# RoverWing-cover-V2_0.net
KiCad netlist of a schematic drawn in EAGLE
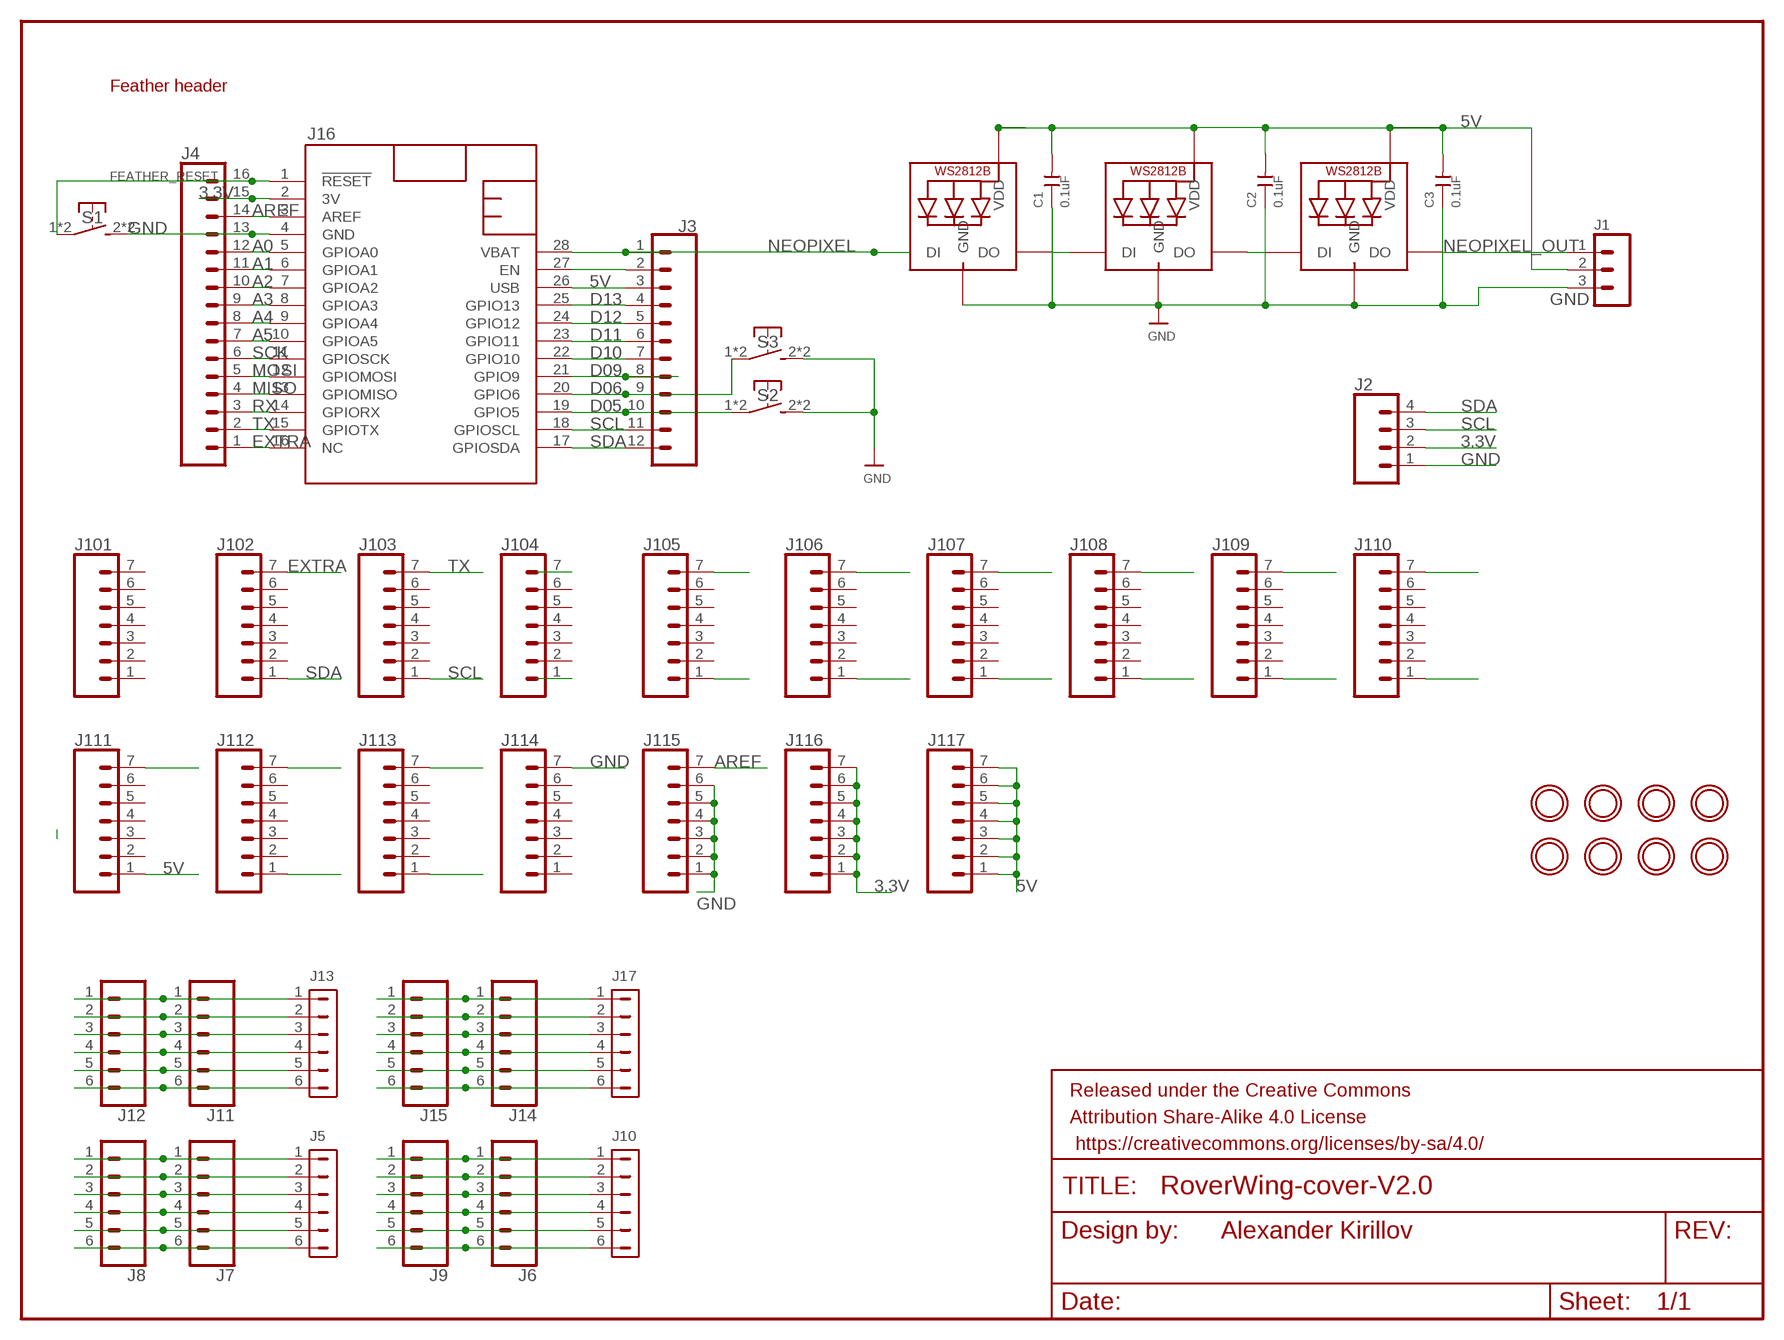
[diagram p0: schematic, sheet 1]

(export (version "E")
  (design (tool "Eeschema 10.0.6"))
  (components
    (comp (ref "C1")
      (value "0.1uF")
      (footprint "eagle-import:C0805")
      (fields (field (name "MF") "AVX") (field (name "MPN") "04025C104KAT2A"))
      (libsource (lib "eagle-import") (part "CAP-CERAMIC-SMD-0805"))
    )
    (comp (ref "C2")
      (value "0.1uF")
      (footprint "eagle-import:C0805")
      (fields (field (name "MF") "AVX") (field (name "MPN") "04025C104KAT2A"))
      (libsource (lib "eagle-import") (part "CAP-CERAMIC-SMD-0805"))
    )
    (comp (ref "C3")
      (value "0.1uF")
      (footprint "eagle-import:C0805")
      (fields (field (name "MF") "AVX") (field (name "MPN") "04025C104KAT2A"))
      (libsource (lib "eagle-import") (part "CAP-CERAMIC-SMD-0805"))
    )
    (comp (ref "FRAME2")
      (value "FRAME-LETTERNO_PACKAGE")
      (footprint "eagle-import:DUMMY")
      (fields (field (name "OC_NEWARK") "unknown") (field (name "DESIGNER") "Nobody"))
      (libsource (lib "eagle-import") (part "FRAME-LETTERNO_PACKAGE"))
    )
    (comp (ref "J1")
      (value "HEADER-PH-3PSIDEENTRY")
      (footprint "eagle-import:S3B-PH-K")
      (fields
        (field (name "PARTNO") "S3B-PH-K-S(LF)(SN)")
        (field (name "MF") "JST (JAPAN SOLDERLESS TERMINALS)")
        (field (name "MPN") "S3B-PH-K-S (LF)(SN)")
      )
      (libsource (lib "eagle-import") (part "HEADER-PH-3PSIDEENTRY"))
    )
    (comp (ref "J2")
      (value "CONN_04")
      (footprint "eagle-import:1X04")
      (libsource (lib "eagle-import") (part "CONN_04"))
    )
    (comp (ref "J3")
      (value "CONN_12NO_SILK")
      (footprint "eagle-import:1X12_NO_SILK")
      (libsource (lib "eagle-import") (part "CONN_12NO_SILK"))
    )
    (comp (ref "J4")
      (value "CONN_161X16_NO_SILK")
      (footprint "eagle-import:1X16_NO_SILK")
      (libsource (lib "eagle-import") (part "CONN_161X16_NO_SILK"))
    )
    (comp (ref "J5")
      (value "HEADER-PH-6PSIDEENTRY")
      (footprint "eagle-import:S6B-PH-K")
      (libsource (lib "eagle-import") (part "HEADER-PH-6PSIDEENTRY"))
    )
    (comp (ref "J6")
      (value "CONN_06NO_SILK_NO_POP")
      (footprint "eagle-import:1X06_NO_SILK")
      (libsource (lib "eagle-import") (part "CONN_06NO_SILK_NO_POP"))
    )
    (comp (ref "J7")
      (value "CONN_06NO_SILK_NO_POP")
      (footprint "eagle-import:1X06_NO_SILK")
      (libsource (lib "eagle-import") (part "CONN_06NO_SILK_NO_POP"))
    )
    (comp (ref "J8")
      (value "CONN_06NO_SILK_NO_POP")
      (footprint "eagle-import:1X06_NO_SILK")
      (libsource (lib "eagle-import") (part "CONN_06NO_SILK_NO_POP"))
    )
    (comp (ref "J9")
      (value "CONN_06NO_SILK_NO_POP")
      (footprint "eagle-import:1X06_NO_SILK")
      (libsource (lib "eagle-import") (part "CONN_06NO_SILK_NO_POP"))
    )
    (comp (ref "J10")
      (value "HEADER-PH-6PSIDEENTRY")
      (footprint "eagle-import:S6B-PH-K")
      (libsource (lib "eagle-import") (part "HEADER-PH-6PSIDEENTRY"))
    )
    (comp (ref "J11")
      (value "CONN_06NO_SILK_NO_POP")
      (footprint "eagle-import:1X06_NO_SILK")
      (libsource (lib "eagle-import") (part "CONN_06NO_SILK_NO_POP"))
    )
    (comp (ref "J12")
      (value "CONN_06NO_SILK_NO_POP")
      (footprint "eagle-import:1X06_NO_SILK")
      (libsource (lib "eagle-import") (part "CONN_06NO_SILK_NO_POP"))
    )
    (comp (ref "J13")
      (value "HEADER-PH-6PSIDEENTRY")
      (footprint "eagle-import:S6B-PH-K")
      (libsource (lib "eagle-import") (part "HEADER-PH-6PSIDEENTRY"))
    )
    (comp (ref "J14")
      (value "CONN_06NO_SILK_NO_POP")
      (footprint "eagle-import:1X06_NO_SILK")
      (libsource (lib "eagle-import") (part "CONN_06NO_SILK_NO_POP"))
    )
    (comp (ref "J15")
      (value "CONN_06NO_SILK_NO_POP")
      (footprint "eagle-import:1X06_NO_SILK")
      (libsource (lib "eagle-import") (part "CONN_06NO_SILK_NO_POP"))
    )
    (comp (ref "J16")
      (value "FEATHERWING_NODIM")
      (footprint "eagle-import:FEATHERWING_DIM")
      (libsource (lib "eagle-import") (part "FEATHERWING_NODIM"))
    )
    (comp (ref "J17")
      (value "HEADER-PH-6PSIDEENTRY")
      (footprint "eagle-import:S6B-PH-K")
      (libsource (lib "eagle-import") (part "HEADER-PH-6PSIDEENTRY"))
    )
    (comp (ref "J101")
      (value "CONN_07NO_SILK")
      (footprint "eagle-import:1X07_NO_SILK")
      (libsource (lib "eagle-import") (part "CONN_07NO_SILK"))
    )
    (comp (ref "J102")
      (value "CONN_07NO_SILK")
      (footprint "eagle-import:1X07_NO_SILK")
      (libsource (lib "eagle-import") (part "CONN_07NO_SILK"))
    )
    (comp (ref "J103")
      (value "CONN_07NO_SILK")
      (footprint "eagle-import:1X07_NO_SILK")
      (libsource (lib "eagle-import") (part "CONN_07NO_SILK"))
    )
    (comp (ref "J104")
      (value "CONN_07NO_SILK")
      (footprint "eagle-import:1X07_NO_SILK")
      (libsource (lib "eagle-import") (part "CONN_07NO_SILK"))
    )
    (comp (ref "J105")
      (value "CONN_07NO_SILK")
      (footprint "eagle-import:1X07_NO_SILK")
      (libsource (lib "eagle-import") (part "CONN_07NO_SILK"))
    )
    (comp (ref "J106")
      (value "CONN_07NO_SILK")
      (footprint "eagle-import:1X07_NO_SILK")
      (libsource (lib "eagle-import") (part "CONN_07NO_SILK"))
    )
    (comp (ref "J107")
      (value "CONN_07NO_SILK")
      (footprint "eagle-import:1X07_NO_SILK")
      (libsource (lib "eagle-import") (part "CONN_07NO_SILK"))
    )
    (comp (ref "J108")
      (value "CONN_07NO_SILK")
      (footprint "eagle-import:1X07_NO_SILK")
      (libsource (lib "eagle-import") (part "CONN_07NO_SILK"))
    )
    (comp (ref "J109")
      (value "CONN_07NO_SILK")
      (footprint "eagle-import:1X07_NO_SILK")
      (libsource (lib "eagle-import") (part "CONN_07NO_SILK"))
    )
    (comp (ref "J110")
      (value "CONN_07NO_SILK")
      (footprint "eagle-import:1X07_NO_SILK")
      (libsource (lib "eagle-import") (part "CONN_07NO_SILK"))
    )
    (comp (ref "J111")
      (value "CONN_07NO_SILK")
      (footprint "eagle-import:1X07_NO_SILK")
      (libsource (lib "eagle-import") (part "CONN_07NO_SILK"))
    )
    (comp (ref "J112")
      (value "CONN_07NO_SILK")
      (footprint "eagle-import:1X07_NO_SILK")
      (libsource (lib "eagle-import") (part "CONN_07NO_SILK"))
    )
    (comp (ref "J113")
      (value "CONN_07NO_SILK")
      (footprint "eagle-import:1X07_NO_SILK")
      (libsource (lib "eagle-import") (part "CONN_07NO_SILK"))
    )
    (comp (ref "J114")
      (value "CONN_07NO_SILK")
      (footprint "eagle-import:1X07_NO_SILK")
      (libsource (lib "eagle-import") (part "CONN_07NO_SILK"))
    )
    (comp (ref "J115")
      (value "CONN_07NO_SILK")
      (footprint "eagle-import:1X07_NO_SILK")
      (libsource (lib "eagle-import") (part "CONN_07NO_SILK"))
    )
    (comp (ref "J116")
      (value "CONN_07NO_SILK")
      (footprint "eagle-import:1X07_NO_SILK")
      (libsource (lib "eagle-import") (part "CONN_07NO_SILK"))
    )
    (comp (ref "J117")
      (value "CONN_07NO_SILK")
      (footprint "eagle-import:1X07_NO_SILK")
      (libsource (lib "eagle-import") (part "CONN_07NO_SILK"))
    )
    (comp (ref "LED1")
      (value "WS2812B3535")
      (footprint "eagle-import:LED3535")
      (fields
        (field (name "MANUFACTURER") "Worldsemi")
        (field (name "PARTNO") "WS2812B-3535 ")
        (field (name "MF") "ADAFRUIT")
      )
      (libsource (lib "eagle-import") (part "WS2812B3535"))
    )
    (comp (ref "LED2")
      (value "WS2812B3535")
      (footprint "eagle-import:LED3535")
      (fields
        (field (name "MANUFACTURER") "Worldsemi")
        (field (name "PARTNO") "WS2812B-3535 ")
        (field (name "MF") "ADAFRUIT")
      )
      (libsource (lib "eagle-import") (part "WS2812B3535"))
    )
    (comp (ref "LED3")
      (value "WS2812B3535")
      (footprint "eagle-import:LED3535")
      (fields
        (field (name "MANUFACTURER") "Worldsemi")
        (field (name "PARTNO") "WS2812B-3535 ")
        (field (name "MF") "ADAFRUIT")
      )
      (libsource (lib "eagle-import") (part "WS2812B3535"))
    )
    (comp (ref "S1")
      (value "SW-TACTILE-4.5X4.5_SMD")
      (footprint "eagle-import:TL3305")
      (fields (field (name "MF") "E-SWITCH") (field (name "MPN") "TL3305AF160QG"))
      (libsource (lib "eagle-import") (part "SW-TACTILE-4.5X4.5_SMD"))
    )
    (comp (ref "S2")
      (value "SW-TACTILE-4.5X4.5_SMD")
      (footprint "eagle-import:TL3305")
      (fields (field (name "MF") "E-SWITCH") (field (name "MPN") "TL3305AF160QG"))
      (libsource (lib "eagle-import") (part "SW-TACTILE-4.5X4.5_SMD"))
    )
    (comp (ref "S3")
      (value "SW-TACTILE-4.5X4.5_SMD")
      (footprint "eagle-import:TL3305")
      (fields (field (name "MF") "E-SWITCH") (field (name "MPN") "TL3305AF160QG"))
      (libsource (lib "eagle-import") (part "SW-TACTILE-4.5X4.5_SMD"))
    )
    (comp (ref "U$3")
      (value "MOUNTINGHOLE3.0_NPH")
      (footprint "eagle-import:MOUNTINGHOLE_3.0_NPH")
      (libsource (lib "eagle-import") (part "MOUNTINGHOLE3.0_NPH"))
    )
    (comp (ref "U$4")
      (value "MOUNTINGHOLE3.0_NPH")
      (footprint "eagle-import:MOUNTINGHOLE_3.0_NPH")
      (libsource (lib "eagle-import") (part "MOUNTINGHOLE3.0_NPH"))
    )
    (comp (ref "U$14")
      (value "MOUNTINGHOLE3.0_NPH")
      (footprint "eagle-import:MOUNTINGHOLE_3.0_NPH")
      (libsource (lib "eagle-import") (part "MOUNTINGHOLE3.0_NPH"))
    )
    (comp (ref "U$15")
      (value "MOUNTINGHOLE3.0_NPH")
      (footprint "eagle-import:MOUNTINGHOLE_3.0_NPH")
      (libsource (lib "eagle-import") (part "MOUNTINGHOLE3.0_NPH"))
    )
    (comp (ref "U$24")
      (value "MOUNTINGHOLE3.0_NPH")
      (footprint "eagle-import:MOUNTINGHOLE_3.0_NPH")
      (libsource (lib "eagle-import") (part "MOUNTINGHOLE3.0_NPH"))
    )
    (comp (ref "U$25")
      (value "MOUNTINGHOLE3.0_NPH")
      (footprint "eagle-import:MOUNTINGHOLE_3.0_NPH")
      (libsource (lib "eagle-import") (part "MOUNTINGHOLE3.0_NPH"))
    )
    (comp (ref "U$26")
      (value "MOUNTINGHOLE3.0_NPH")
      (footprint "eagle-import:MOUNTINGHOLE_3.0_NPH")
      (libsource (lib "eagle-import") (part "MOUNTINGHOLE3.0_NPH"))
    )
    (comp (ref "U$27")
      (value "MOUNTINGHOLE3.0_NPH")
      (footprint "eagle-import:MOUNTINGHOLE_3.0_NPH")
      (libsource (lib "eagle-import") (part "MOUNTINGHOLE3.0_NPH"))
    )
  )
  (nets
    (net (code "1") (name "/3.3V") (class "Default")
      (node (ref "J116") (pin "1") (pinfunction "1_1") (pintype "passive"))
      (node (ref "J116") (pin "2") (pinfunction "2_2") (pintype "passive"))
      (node (ref "J116") (pin "3") (pinfunction "3_3") (pintype "passive"))
      (node (ref "J116") (pin "4") (pinfunction "4_4") (pintype "passive"))
      (node (ref "J116") (pin "5") (pinfunction "5_5") (pintype "passive"))
      (node (ref "J116") (pin "6") (pinfunction "6_6") (pintype "passive"))
      (node (ref "J116") (pin "7") (pinfunction "7_7") (pintype "passive"))
      (node (ref "J16") (pin "2") (pinfunction "3V_2") (pintype "power_in"))
      (node (ref "J2") (pin "2") (pinfunction "2_2") (pintype "passive"))
      (node (ref "J4") (pin "15") (pinfunction "15_15") (pintype "passive"))
    )
    (net (code "2") (name "/5V") (class "Default")
      (node (ref "C1") (pin "2") (pinfunction "2_2") (pintype "passive"))
      (node (ref "C2") (pin "2") (pinfunction "2_2") (pintype "passive"))
      (node (ref "C3") (pin "2") (pinfunction "2_2") (pintype "passive"))
      (node (ref "J1") (pin "2") (pinfunction "2_2") (pintype "passive"))
      (node (ref "J111") (pin "1") (pinfunction "1_1") (pintype "passive"))
      (node (ref "J117") (pin "1") (pinfunction "1_1") (pintype "passive"))
      (node (ref "J117") (pin "2") (pinfunction "2_2") (pintype "passive"))
      (node (ref "J117") (pin "3") (pinfunction "3_3") (pintype "passive"))
      (node (ref "J117") (pin "4") (pinfunction "4_4") (pintype "passive"))
      (node (ref "J117") (pin "5") (pinfunction "5_5") (pintype "passive"))
      (node (ref "J117") (pin "6") (pinfunction "6_6") (pintype "passive"))
      (node (ref "J117") (pin "7") (pinfunction "7_7") (pintype "passive"))
      (node (ref "J16") (pin "26") (pinfunction "USB_26") (pintype "power_in"))
      (node (ref "J3") (pin "3") (pinfunction "3_3") (pintype "passive"))
      (node (ref "LED1") (pin "3") (pinfunction "VDD_3") (pintype "power_in"))
      (node (ref "LED2") (pin "3") (pinfunction "VDD_3") (pintype "power_in"))
      (node (ref "LED3") (pin "3") (pinfunction "VDD_3") (pintype "power_in"))
    )
    (net (code "3") (name "/A0") (class "Default")
      (node (ref "J113") (pin "7") (pinfunction "7_7") (pintype "passive"))
      (node (ref "J16") (pin "5") (pinfunction "GPIOA0_5") (pintype "bidirectional"))
      (node (ref "J4") (pin "12") (pinfunction "12_12") (pintype "passive"))
    )
    (net (code "4") (name "/A1") (class "Default")
      (node (ref "J112") (pin "7") (pinfunction "7_7") (pintype "passive"))
      (node (ref "J16") (pin "6") (pinfunction "GPIOA1_6") (pintype "bidirectional"))
      (node (ref "J4") (pin "11") (pinfunction "11_11") (pintype "passive"))
    )
    (net (code "5") (name "/A2") (class "Default")
      (node (ref "J111") (pin "7") (pinfunction "7_7") (pintype "passive"))
      (node (ref "J16") (pin "7") (pinfunction "GPIOA2_7") (pintype "bidirectional"))
      (node (ref "J4") (pin "10") (pinfunction "10_10") (pintype "passive"))
    )
    (net (code "6") (name "/A3") (class "Default")
      (node (ref "J110") (pin "7") (pinfunction "7_7") (pintype "passive"))
      (node (ref "J16") (pin "8") (pinfunction "GPIOA3_8") (pintype "bidirectional"))
      (node (ref "J4") (pin "9") (pinfunction "9_9") (pintype "passive"))
    )
    (net (code "7") (name "/A4") (class "Default")
      (node (ref "J109") (pin "7") (pinfunction "7_7") (pintype "passive"))
      (node (ref "J16") (pin "9") (pinfunction "GPIOA4_9") (pintype "bidirectional"))
      (node (ref "J4") (pin "8") (pinfunction "8_8") (pintype "passive"))
    )
    (net (code "8") (name "/A5") (class "Default")
      (node (ref "J108") (pin "7") (pinfunction "7_7") (pintype "passive"))
      (node (ref "J16") (pin "10") (pinfunction "GPIOA5_10") (pintype "bidirectional"))
      (node (ref "J4") (pin "7") (pinfunction "7_7") (pintype "passive"))
    )
    (net (code "9") (name "/AREF") (class "Default")
      (node (ref "J115") (pin "7") (pinfunction "7_7") (pintype "passive"))
      (node (ref "J16") (pin "3") (pinfunction "AREF_3") (pintype "passive"))
      (node (ref "J4") (pin "14") (pinfunction "14_14") (pintype "passive"))
    )
    (net (code "10") (name "/D05") (class "Default")
      (node (ref "J104") (pin "1") (pinfunction "1_1") (pintype "passive"))
      (node (ref "J16") (pin "19") (pinfunction "GPIO5_19") (pintype "bidirectional"))
      (node (ref "J3") (pin "10") (pinfunction "10_10") (pintype "passive"))
      (node (ref "S2") (pin "1") (pinfunction "P1_1") (pintype "passive"))
      (node (ref "S2") (pin "4") (pinfunction "P1_4") (pintype "passive"))
    )
    (net (code "11") (name "/D06") (class "Default")
      (node (ref "J105") (pin "1") (pinfunction "1_1") (pintype "passive"))
      (node (ref "J16") (pin "20") (pinfunction "GPIO6_20") (pintype "bidirectional"))
      (node (ref "J3") (pin "9") (pinfunction "9_9") (pintype "passive"))
      (node (ref "S3") (pin "1") (pinfunction "P1_1") (pintype "passive"))
      (node (ref "S3") (pin "4") (pinfunction "P1_4") (pintype "passive"))
    )
    (net (code "12") (name "/D09") (class "Default")
      (node (ref "J106") (pin "1") (pinfunction "1_1") (pintype "passive"))
      (node (ref "J16") (pin "21") (pinfunction "GPIO9_21") (pintype "bidirectional"))
      (node (ref "J3") (pin "8") (pinfunction "8_8") (pintype "passive"))
    )
    (net (code "13") (name "/D10") (class "Default")
      (node (ref "J107") (pin "1") (pinfunction "1_1") (pintype "passive"))
      (node (ref "J16") (pin "22") (pinfunction "GPIO10_22") (pintype "bidirectional"))
      (node (ref "J3") (pin "7") (pinfunction "7_7") (pintype "passive"))
    )
    (net (code "14") (name "/D11") (class "Default")
      (node (ref "J108") (pin "1") (pinfunction "1_1") (pintype "passive"))
      (node (ref "J16") (pin "23") (pinfunction "GPIO11_23") (pintype "bidirectional"))
      (node (ref "J3") (pin "6") (pinfunction "6_6") (pintype "passive"))
    )
    (net (code "15") (name "/D12") (class "Default")
      (node (ref "J109") (pin "1") (pinfunction "1_1") (pintype "passive"))
      (node (ref "J16") (pin "24") (pinfunction "GPIO12_24") (pintype "bidirectional"))
      (node (ref "J3") (pin "5") (pinfunction "5_5") (pintype "passive"))
    )
    (net (code "16") (name "/D13") (class "Default")
      (node (ref "J110") (pin "1") (pinfunction "1_1") (pintype "passive"))
      (node (ref "J16") (pin "25") (pinfunction "GPIO13_25") (pintype "bidirectional"))
      (node (ref "J3") (pin "4") (pinfunction "4_4") (pintype "passive"))
    )
    (net (code "17") (name "/EXTRA") (class "Default")
      (node (ref "J102") (pin "7") (pinfunction "7_7") (pintype "passive"))
      (node (ref "J16") (pin "16") (pinfunction "NC_16") (pintype "passive"))
      (node (ref "J4") (pin "1") (pinfunction "1_1") (pintype "passive"))
    )
    (net (code "18") (name "/FEATHER_RESET") (class "Default")
      (node (ref "J16") (pin "1") (pinfunction "~{RESET}_1") (pintype "input"))
      (node (ref "J4") (pin "16") (pinfunction "16_16") (pintype "passive"))
      (node (ref "S1") (pin "1") (pinfunction "P1_1") (pintype "passive"))
      (node (ref "S1") (pin "4") (pinfunction "P1_4") (pintype "passive"))
    )
    (net (code "19") (name "/MISO") (class "Default")
      (node (ref "J105") (pin "7") (pinfunction "7_7") (pintype "passive"))
      (node (ref "J16") (pin "13") (pinfunction "GPIOMISO_13") (pintype "bidirectional"))
      (node (ref "J4") (pin "4") (pinfunction "4_4") (pintype "passive"))
    )
    (net (code "20") (name "/MOSI") (class "Default")
      (node (ref "J106") (pin "7") (pinfunction "7_7") (pintype "passive"))
      (node (ref "J16") (pin "12") (pinfunction "GPIOMOSI_12") (pintype "bidirectional"))
      (node (ref "J4") (pin "5") (pinfunction "5_5") (pintype "passive"))
    )
    (net (code "21") (name "/N$37") (class "Default")
      (node (ref "J112") (pin "1") (pinfunction "1_1") (pintype "passive"))
      (node (ref "J16") (pin "27") (pinfunction "EN_27") (pintype "passive"))
      (node (ref "J3") (pin "2") (pinfunction "2_2") (pintype "passive"))
    )
    (net (code "22") (name "/NEOPIXEL") (class "Default")
      (node (ref "J16") (pin "28") (pinfunction "VBAT_28") (pintype "power_in"))
      (node (ref "J3") (pin "1") (pinfunction "1_1") (pintype "passive"))
      (node (ref "LED1") (pin "2") (pinfunction "DI_2") (pintype "input"))
    )
    (net (code "23") (name "/NEOPIXEL_OUT") (class "Default")
      (node (ref "J1") (pin "1") (pinfunction "1_1") (pintype "passive"))
      (node (ref "LED3") (pin "4") (pinfunction "DO_4") (pintype "output"))
    )
    (net (code "24") (name "/RX") (class "Default")
      (node (ref "J104") (pin "7") (pinfunction "7_7") (pintype "passive"))
      (node (ref "J16") (pin "14") (pinfunction "GPIORX_14") (pintype "bidirectional"))
      (node (ref "J4") (pin "3") (pinfunction "3_3") (pintype "passive"))
    )
    (net (code "25") (name "/SCK") (class "Default")
      (node (ref "J107") (pin "7") (pinfunction "7_7") (pintype "passive"))
      (node (ref "J16") (pin "11") (pinfunction "GPIOSCK_11") (pintype "bidirectional"))
      (node (ref "J4") (pin "6") (pinfunction "6_6") (pintype "passive"))
    )
    (net (code "26") (name "/SCL") (class "Default")
      (node (ref "J103") (pin "1") (pinfunction "1_1") (pintype "passive"))
      (node (ref "J16") (pin "18") (pinfunction "GPIOSCL_18") (pintype "bidirectional"))
      (node (ref "J2") (pin "3") (pinfunction "3_3") (pintype "passive"))
      (node (ref "J3") (pin "11") (pinfunction "11_11") (pintype "passive"))
    )
    (net (code "27") (name "/SDA") (class "Default")
      (node (ref "J102") (pin "1") (pinfunction "1_1") (pintype "passive"))
      (node (ref "J16") (pin "17") (pinfunction "GPIOSDA_17") (pintype "bidirectional"))
      (node (ref "J2") (pin "4") (pinfunction "4_4") (pintype "passive"))
      (node (ref "J3") (pin "12") (pinfunction "12_12") (pintype "passive"))
    )
    (net (code "28") (name "/TX") (class "Default")
      (node (ref "J103") (pin "7") (pinfunction "7_7") (pintype "passive"))
      (node (ref "J16") (pin "15") (pinfunction "GPIOTX_15") (pintype "bidirectional"))
      (node (ref "J4") (pin "2") (pinfunction "2_2") (pintype "passive"))
    )
    (net (code "29") (name "GND") (class "Default")
      (node (ref "C1") (pin "1") (pinfunction "1_1") (pintype "passive"))
      (node (ref "C2") (pin "1") (pinfunction "1_1") (pintype "passive"))
      (node (ref "C3") (pin "1") (pinfunction "1_1") (pintype "passive"))
      (node (ref "J1") (pin "3") (pinfunction "3_3") (pintype "passive"))
      (node (ref "J114") (pin "7") (pinfunction "7_7") (pintype "passive"))
      (node (ref "J115") (pin "1") (pinfunction "1_1") (pintype "passive"))
      (node (ref "J115") (pin "2") (pinfunction "2_2") (pintype "passive"))
      (node (ref "J115") (pin "3") (pinfunction "3_3") (pintype "passive"))
      (node (ref "J115") (pin "4") (pinfunction "4_4") (pintype "passive"))
      (node (ref "J115") (pin "5") (pinfunction "5_5") (pintype "passive"))
      (node (ref "J115") (pin "6") (pinfunction "6_6") (pintype "passive"))
      (node (ref "J16") (pin "4") (pinfunction "GND_4") (pintype "power_in"))
      (node (ref "J2") (pin "1") (pinfunction "1_1") (pintype "passive"))
      (node (ref "J4") (pin "13") (pinfunction "13_13") (pintype "passive"))
      (node (ref "LED1") (pin "1") (pinfunction "GND_1") (pintype "power_in"))
      (node (ref "LED2") (pin "1") (pinfunction "GND_1") (pintype "power_in"))
      (node (ref "LED3") (pin "1") (pinfunction "GND_1") (pintype "power_in"))
      (node (ref "S1") (pin "2") (pinfunction "S1_2") (pintype "passive"))
      (node (ref "S1") (pin "3") (pinfunction "S1_3") (pintype "passive"))
      (node (ref "S2") (pin "2") (pinfunction "S1_2") (pintype "passive"))
      (node (ref "S2") (pin "3") (pinfunction "S1_3") (pintype "passive"))
      (node (ref "S3") (pin "2") (pinfunction "S1_2") (pintype "passive"))
      (node (ref "S3") (pin "3") (pinfunction "S1_3") (pintype "passive"))
    )
    (net (code "30") (name "Net-(J5-Pad1)") (class "Default")
      (node (ref "J5") (pin "1") (pinfunction "1_1") (pintype "passive"))
      (node (ref "J7") (pin "1") (pinfunction "1_1") (pintype "passive"))
      (node (ref "J8") (pin "1") (pinfunction "1_1") (pintype "passive"))
    )
    (net (code "31") (name "Net-(J5-Pad2)") (class "Default")
      (node (ref "J5") (pin "2") (pinfunction "2_2") (pintype "passive"))
      (node (ref "J7") (pin "2") (pinfunction "2_2") (pintype "passive"))
      (node (ref "J8") (pin "2") (pinfunction "2_2") (pintype "passive"))
    )
    (net (code "32") (name "Net-(J5-Pad3)") (class "Default")
      (node (ref "J5") (pin "3") (pinfunction "3_3") (pintype "passive"))
      (node (ref "J7") (pin "3") (pinfunction "3_3") (pintype "passive"))
      (node (ref "J8") (pin "3") (pinfunction "3_3") (pintype "passive"))
    )
    (net (code "33") (name "Net-(J5-Pad4)") (class "Default")
      (node (ref "J5") (pin "4") (pinfunction "4_4") (pintype "passive"))
      (node (ref "J7") (pin "4") (pinfunction "4_4") (pintype "passive"))
      (node (ref "J8") (pin "4") (pinfunction "4_4") (pintype "passive"))
    )
    (net (code "34") (name "Net-(J5-Pad5)") (class "Default")
      (node (ref "J5") (pin "5") (pinfunction "5_5") (pintype "passive"))
      (node (ref "J7") (pin "5") (pinfunction "5_5") (pintype "passive"))
      (node (ref "J8") (pin "5") (pinfunction "5_5") (pintype "passive"))
    )
    (net (code "35") (name "Net-(J5-Pad6)") (class "Default")
      (node (ref "J5") (pin "6") (pinfunction "6_6") (pintype "passive"))
      (node (ref "J7") (pin "6") (pinfunction "6_6") (pintype "passive"))
      (node (ref "J8") (pin "6") (pinfunction "6_6") (pintype "passive"))
    )
    (net (code "36") (name "Net-(J10-Pad1)") (class "Default")
      (node (ref "J10") (pin "1") (pinfunction "1_1") (pintype "passive"))
      (node (ref "J6") (pin "1") (pinfunction "1_1") (pintype "passive"))
      (node (ref "J9") (pin "1") (pinfunction "1_1") (pintype "passive"))
    )
    (net (code "37") (name "Net-(J10-Pad2)") (class "Default")
      (node (ref "J10") (pin "2") (pinfunction "2_2") (pintype "passive"))
      (node (ref "J6") (pin "2") (pinfunction "2_2") (pintype "passive"))
      (node (ref "J9") (pin "2") (pinfunction "2_2") (pintype "passive"))
    )
    (net (code "38") (name "Net-(J10-Pad3)") (class "Default")
      (node (ref "J10") (pin "3") (pinfunction "3_3") (pintype "passive"))
      (node (ref "J6") (pin "3") (pinfunction "3_3") (pintype "passive"))
      (node (ref "J9") (pin "3") (pinfunction "3_3") (pintype "passive"))
    )
    (net (code "39") (name "Net-(J10-Pad4)") (class "Default")
      (node (ref "J10") (pin "4") (pinfunction "4_4") (pintype "passive"))
      (node (ref "J6") (pin "4") (pinfunction "4_4") (pintype "passive"))
      (node (ref "J9") (pin "4") (pinfunction "4_4") (pintype "passive"))
    )
    (net (code "40") (name "Net-(J10-Pad5)") (class "Default")
      (node (ref "J10") (pin "5") (pinfunction "5_5") (pintype "passive"))
      (node (ref "J6") (pin "5") (pinfunction "5_5") (pintype "passive"))
      (node (ref "J9") (pin "5") (pinfunction "5_5") (pintype "passive"))
    )
    (net (code "41") (name "Net-(J10-Pad6)") (class "Default")
      (node (ref "J10") (pin "6") (pinfunction "6_6") (pintype "passive"))
      (node (ref "J6") (pin "6") (pinfunction "6_6") (pintype "passive"))
      (node (ref "J9") (pin "6") (pinfunction "6_6") (pintype "passive"))
    )
    (net (code "42") (name "Net-(J11-Pad1)") (class "Default")
      (node (ref "J11") (pin "1") (pinfunction "1_1") (pintype "passive"))
      (node (ref "J12") (pin "1") (pinfunction "1_1") (pintype "passive"))
      (node (ref "J13") (pin "1") (pinfunction "1_1") (pintype "passive"))
    )
    (net (code "43") (name "Net-(J11-Pad2)") (class "Default")
      (node (ref "J11") (pin "2") (pinfunction "2_2") (pintype "passive"))
      (node (ref "J12") (pin "2") (pinfunction "2_2") (pintype "passive"))
      (node (ref "J13") (pin "2") (pinfunction "2_2") (pintype "passive"))
    )
    (net (code "44") (name "Net-(J11-Pad3)") (class "Default")
      (node (ref "J11") (pin "3") (pinfunction "3_3") (pintype "passive"))
      (node (ref "J12") (pin "3") (pinfunction "3_3") (pintype "passive"))
      (node (ref "J13") (pin "3") (pinfunction "3_3") (pintype "passive"))
    )
    (net (code "45") (name "Net-(J11-Pad4)") (class "Default")
      (node (ref "J11") (pin "4") (pinfunction "4_4") (pintype "passive"))
      (node (ref "J12") (pin "4") (pinfunction "4_4") (pintype "passive"))
      (node (ref "J13") (pin "4") (pinfunction "4_4") (pintype "passive"))
    )
    (net (code "46") (name "Net-(J11-Pad5)") (class "Default")
      (node (ref "J11") (pin "5") (pinfunction "5_5") (pintype "passive"))
      (node (ref "J12") (pin "5") (pinfunction "5_5") (pintype "passive"))
      (node (ref "J13") (pin "5") (pinfunction "5_5") (pintype "passive"))
    )
    (net (code "47") (name "Net-(J11-Pad6)") (class "Default")
      (node (ref "J11") (pin "6") (pinfunction "6_6") (pintype "passive"))
      (node (ref "J12") (pin "6") (pinfunction "6_6") (pintype "passive"))
      (node (ref "J13") (pin "6") (pinfunction "6_6") (pintype "passive"))
    )
    (net (code "48") (name "Net-(J14-Pad1)") (class "Default")
      (node (ref "J14") (pin "1") (pinfunction "1_1") (pintype "passive"))
      (node (ref "J15") (pin "1") (pinfunction "1_1") (pintype "passive"))
      (node (ref "J17") (pin "1") (pinfunction "1_1") (pintype "passive"))
    )
    (net (code "49") (name "Net-(J14-Pad2)") (class "Default")
      (node (ref "J14") (pin "2") (pinfunction "2_2") (pintype "passive"))
      (node (ref "J15") (pin "2") (pinfunction "2_2") (pintype "passive"))
      (node (ref "J17") (pin "2") (pinfunction "2_2") (pintype "passive"))
    )
    (net (code "50") (name "Net-(J14-Pad3)") (class "Default")
      (node (ref "J14") (pin "3") (pinfunction "3_3") (pintype "passive"))
      (node (ref "J15") (pin "3") (pinfunction "3_3") (pintype "passive"))
      (node (ref "J17") (pin "3") (pinfunction "3_3") (pintype "passive"))
    )
    (net (code "51") (name "Net-(J14-Pad4)") (class "Default")
      (node (ref "J14") (pin "4") (pinfunction "4_4") (pintype "passive"))
      (node (ref "J15") (pin "4") (pinfunction "4_4") (pintype "passive"))
      (node (ref "J17") (pin "4") (pinfunction "4_4") (pintype "passive"))
    )
    (net (code "52") (name "Net-(J14-Pad5)") (class "Default")
      (node (ref "J14") (pin "5") (pinfunction "5_5") (pintype "passive"))
      (node (ref "J15") (pin "5") (pinfunction "5_5") (pintype "passive"))
      (node (ref "J17") (pin "5") (pinfunction "5_5") (pintype "passive"))
    )
    (net (code "53") (name "Net-(J14-Pad6)") (class "Default")
      (node (ref "J14") (pin "6") (pinfunction "6_6") (pintype "passive"))
      (node (ref "J15") (pin "6") (pinfunction "6_6") (pintype "passive"))
      (node (ref "J17") (pin "6") (pinfunction "6_6") (pintype "passive"))
    )
    (net (code "54") (name "Net-(LED1-DO)") (class "Default")
      (node (ref "LED1") (pin "4") (pinfunction "DO_4") (pintype "output"))
      (node (ref "LED2") (pin "2") (pinfunction "DI_2") (pintype "input"))
    )
    (net (code "55") (name "Net-(LED2-DO)") (class "Default")
      (node (ref "LED2") (pin "4") (pinfunction "DO_4") (pintype "output"))
      (node (ref "LED3") (pin "2") (pinfunction "DI_2") (pintype "input"))
    )
    (net (code "56") (name "unconnected-(J101-Pad1)") (class "Default")
      (node (ref "J101") (pin "1") (pinfunction "1_1") (pintype "passive"))
    )
    (net (code "57") (name "unconnected-(J101-Pad2)") (class "Default")
      (node (ref "J101") (pin "2") (pinfunction "2_2") (pintype "passive"))
    )
    (net (code "58") (name "unconnected-(J101-Pad3)") (class "Default")
      (node (ref "J101") (pin "3") (pinfunction "3_3") (pintype "passive"))
    )
    (net (code "59") (name "unconnected-(J101-Pad4)") (class "Default")
      (node (ref "J101") (pin "4") (pinfunction "4_4") (pintype "passive"))
    )
    (net (code "60") (name "unconnected-(J101-Pad5)") (class "Default")
      (node (ref "J101") (pin "5") (pinfunction "5_5") (pintype "passive"))
    )
    (net (code "61") (name "unconnected-(J101-Pad6)") (class "Default")
      (node (ref "J101") (pin "6") (pinfunction "6_6") (pintype "passive"))
    )
    (net (code "62") (name "unconnected-(J101-Pad7)") (class "Default")
      (node (ref "J101") (pin "7") (pinfunction "7_7") (pintype "passive"))
    )
    (net (code "63") (name "unconnected-(J102-Pad2)") (class "Default")
      (node (ref "J102") (pin "2") (pinfunction "2_2") (pintype "passive"))
    )
    (net (code "64") (name "unconnected-(J102-Pad3)") (class "Default")
      (node (ref "J102") (pin "3") (pinfunction "3_3") (pintype "passive"))
    )
    (net (code "65") (name "unconnected-(J102-Pad4)") (class "Default")
      (node (ref "J102") (pin "4") (pinfunction "4_4") (pintype "passive"))
    )
    (net (code "66") (name "unconnected-(J102-Pad5)") (class "Default")
      (node (ref "J102") (pin "5") (pinfunction "5_5") (pintype "passive"))
    )
    (net (code "67") (name "unconnected-(J102-Pad6)") (class "Default")
      (node (ref "J102") (pin "6") (pinfunction "6_6") (pintype "passive"))
    )
    (net (code "68") (name "unconnected-(J103-Pad2)") (class "Default")
      (node (ref "J103") (pin "2") (pinfunction "2_2") (pintype "passive"))
    )
    (net (code "69") (name "unconnected-(J103-Pad3)") (class "Default")
      (node (ref "J103") (pin "3") (pinfunction "3_3") (pintype "passive"))
    )
    (net (code "70") (name "unconnected-(J103-Pad4)") (class "Default")
      (node (ref "J103") (pin "4") (pinfunction "4_4") (pintype "passive"))
    )
    (net (code "71") (name "unconnected-(J103-Pad5)") (class "Default")
      (node (ref "J103") (pin "5") (pinfunction "5_5") (pintype "passive"))
    )
    (net (code "72") (name "unconnected-(J103-Pad6)") (class "Default")
      (node (ref "J103") (pin "6") (pinfunction "6_6") (pintype "passive"))
    )
    (net (code "73") (name "unconnected-(J104-Pad2)") (class "Default")
      (node (ref "J104") (pin "2") (pinfunction "2_2") (pintype "passive"))
    )
    (net (code "74") (name "unconnected-(J104-Pad3)") (class "Default")
      (node (ref "J104") (pin "3") (pinfunction "3_3") (pintype "passive"))
    )
    (net (code "75") (name "unconnected-(J104-Pad4)") (class "Default")
      (node (ref "J104") (pin "4") (pinfunction "4_4") (pintype "passive"))
    )
    (net (code "76") (name "unconnected-(J104-Pad5)") (class "Default")
      (node (ref "J104") (pin "5") (pinfunction "5_5") (pintype "passive"))
    )
    (net (code "77") (name "unconnected-(J104-Pad6)") (class "Default")
      (node (ref "J104") (pin "6") (pinfunction "6_6") (pintype "passive"))
    )
    (net (code "78") (name "unconnected-(J105-Pad2)") (class "Default")
      (node (ref "J105") (pin "2") (pinfunction "2_2") (pintype "passive"))
    )
    (net (code "79") (name "unconnected-(J105-Pad3)") (class "Default")
      (node (ref "J105") (pin "3") (pinfunction "3_3") (pintype "passive"))
    )
    (net (code "80") (name "unconnected-(J105-Pad4)") (class "Default")
      (node (ref "J105") (pin "4") (pinfunction "4_4") (pintype "passive"))
    )
    (net (code "81") (name "unconnected-(J105-Pad5)") (class "Default")
      (node (ref "J105") (pin "5") (pinfunction "5_5") (pintype "passive"))
    )
    (net (code "82") (name "unconnected-(J105-Pad6)") (class "Default")
      (node (ref "J105") (pin "6") (pinfunction "6_6") (pintype "passive"))
    )
    (net (code "83") (name "unconnected-(J106-Pad2)") (class "Default")
      (node (ref "J106") (pin "2") (pinfunction "2_2") (pintype "passive"))
    )
    (net (code "84") (name "unconnected-(J106-Pad3)") (class "Default")
      (node (ref "J106") (pin "3") (pinfunction "3_3") (pintype "passive"))
    )
    (net (code "85") (name "unconnected-(J106-Pad4)") (class "Default")
      (node (ref "J106") (pin "4") (pinfunction "4_4") (pintype "passive"))
    )
    (net (code "86") (name "unconnected-(J106-Pad5)") (class "Default")
      (node (ref "J106") (pin "5") (pinfunction "5_5") (pintype "passive"))
    )
    (net (code "87") (name "unconnected-(J106-Pad6)") (class "Default")
      (node (ref "J106") (pin "6") (pinfunction "6_6") (pintype "passive"))
    )
    (net (code "88") (name "unconnected-(J107-Pad2)") (class "Default")
      (node (ref "J107") (pin "2") (pinfunction "2_2") (pintype "passive"))
    )
    (net (code "89") (name "unconnected-(J107-Pad3)") (class "Default")
      (node (ref "J107") (pin "3") (pinfunction "3_3") (pintype "passive"))
    )
    (net (code "90") (name "unconnected-(J107-Pad4)") (class "Default")
      (node (ref "J107") (pin "4") (pinfunction "4_4") (pintype "passive"))
    )
    (net (code "91") (name "unconnected-(J107-Pad5)") (class "Default")
      (node (ref "J107") (pin "5") (pinfunction "5_5") (pintype "passive"))
    )
    (net (code "92") (name "unconnected-(J107-Pad6)") (class "Default")
      (node (ref "J107") (pin "6") (pinfunction "6_6") (pintype "passive"))
    )
    (net (code "93") (name "unconnected-(J108-Pad2)") (class "Default")
      (node (ref "J108") (pin "2") (pinfunction "2_2") (pintype "passive"))
    )
    (net (code "94") (name "unconnected-(J108-Pad3)") (class "Default")
      (node (ref "J108") (pin "3") (pinfunction "3_3") (pintype "passive"))
    )
    (net (code "95") (name "unconnected-(J108-Pad4)") (class "Default")
      (node (ref "J108") (pin "4") (pinfunction "4_4") (pintype "passive"))
    )
    (net (code "96") (name "unconnected-(J108-Pad5)") (class "Default")
      (node (ref "J108") (pin "5") (pinfunction "5_5") (pintype "passive"))
    )
    (net (code "97") (name "unconnected-(J108-Pad6)") (class "Default")
      (node (ref "J108") (pin "6") (pinfunction "6_6") (pintype "passive"))
    )
    (net (code "98") (name "unconnected-(J109-Pad2)") (class "Default")
      (node (ref "J109") (pin "2") (pinfunction "2_2") (pintype "passive"))
    )
    (net (code "99") (name "unconnected-(J109-Pad3)") (class "Default")
      (node (ref "J109") (pin "3") (pinfunction "3_3") (pintype "passive"))
    )
    (net (code "100") (name "unconnected-(J109-Pad4)") (class "Default")
      (node (ref "J109") (pin "4") (pinfunction "4_4") (pintype "passive"))
    )
    (net (code "101") (name "unconnected-(J109-Pad5)") (class "Default")
      (node (ref "J109") (pin "5") (pinfunction "5_5") (pintype "passive"))
    )
    (net (code "102") (name "unconnected-(J109-Pad6)") (class "Default")
      (node (ref "J109") (pin "6") (pinfunction "6_6") (pintype "passive"))
    )
    (net (code "103") (name "unconnected-(J110-Pad2)") (class "Default")
      (node (ref "J110") (pin "2") (pinfunction "2_2") (pintype "passive"))
    )
    (net (code "104") (name "unconnected-(J110-Pad3)") (class "Default")
      (node (ref "J110") (pin "3") (pinfunction "3_3") (pintype "passive"))
    )
    (net (code "105") (name "unconnected-(J110-Pad4)") (class "Default")
      (node (ref "J110") (pin "4") (pinfunction "4_4") (pintype "passive"))
    )
    (net (code "106") (name "unconnected-(J110-Pad5)") (class "Default")
      (node (ref "J110") (pin "5") (pinfunction "5_5") (pintype "passive"))
    )
    (net (code "107") (name "unconnected-(J110-Pad6)") (class "Default")
      (node (ref "J110") (pin "6") (pinfunction "6_6") (pintype "passive"))
    )
    (net (code "108") (name "unconnected-(J111-Pad2)") (class "Default")
      (node (ref "J111") (pin "2") (pinfunction "2_2") (pintype "passive"))
    )
    (net (code "109") (name "unconnected-(J111-Pad3)") (class "Default")
      (node (ref "J111") (pin "3") (pinfunction "3_3") (pintype "passive"))
    )
    (net (code "110") (name "unconnected-(J111-Pad4)") (class "Default")
      (node (ref "J111") (pin "4") (pinfunction "4_4") (pintype "passive"))
    )
    (net (code "111") (name "unconnected-(J111-Pad5)") (class "Default")
      (node (ref "J111") (pin "5") (pinfunction "5_5") (pintype "passive"))
    )
    (net (code "112") (name "unconnected-(J111-Pad6)") (class "Default")
      (node (ref "J111") (pin "6") (pinfunction "6_6") (pintype "passive"))
    )
    (net (code "113") (name "unconnected-(J112-Pad2)") (class "Default")
      (node (ref "J112") (pin "2") (pinfunction "2_2") (pintype "passive"))
    )
    (net (code "114") (name "unconnected-(J112-Pad3)") (class "Default")
      (node (ref "J112") (pin "3") (pinfunction "3_3") (pintype "passive"))
    )
    (net (code "115") (name "unconnected-(J112-Pad4)") (class "Default")
      (node (ref "J112") (pin "4") (pinfunction "4_4") (pintype "passive"))
    )
    (net (code "116") (name "unconnected-(J112-Pad5)") (class "Default")
      (node (ref "J112") (pin "5") (pinfunction "5_5") (pintype "passive"))
    )
    (net (code "117") (name "unconnected-(J112-Pad6)") (class "Default")
      (node (ref "J112") (pin "6") (pinfunction "6_6") (pintype "passive"))
    )
    (net (code "118") (name "unconnected-(J113-Pad1)") (class "Default")
      (node (ref "J113") (pin "1") (pinfunction "1_1") (pintype "passive"))
    )
    (net (code "119") (name "unconnected-(J113-Pad2)") (class "Default")
      (node (ref "J113") (pin "2") (pinfunction "2_2") (pintype "passive"))
    )
    (net (code "120") (name "unconnected-(J113-Pad3)") (class "Default")
      (node (ref "J113") (pin "3") (pinfunction "3_3") (pintype "passive"))
    )
    (net (code "121") (name "unconnected-(J113-Pad4)") (class "Default")
      (node (ref "J113") (pin "4") (pinfunction "4_4") (pintype "passive"))
    )
    (net (code "122") (name "unconnected-(J113-Pad5)") (class "Default")
      (node (ref "J113") (pin "5") (pinfunction "5_5") (pintype "passive"))
    )
    (net (code "123") (name "unconnected-(J113-Pad6)") (class "Default")
      (node (ref "J113") (pin "6") (pinfunction "6_6") (pintype "passive"))
    )
    (net (code "124") (name "unconnected-(J114-Pad1)") (class "Default")
      (node (ref "J114") (pin "1") (pinfunction "1_1") (pintype "passive"))
    )
    (net (code "125") (name "unconnected-(J114-Pad2)") (class "Default")
      (node (ref "J114") (pin "2") (pinfunction "2_2") (pintype "passive"))
    )
    (net (code "126") (name "unconnected-(J114-Pad3)") (class "Default")
      (node (ref "J114") (pin "3") (pinfunction "3_3") (pintype "passive"))
    )
    (net (code "127") (name "unconnected-(J114-Pad4)") (class "Default")
      (node (ref "J114") (pin "4") (pinfunction "4_4") (pintype "passive"))
    )
    (net (code "128") (name "unconnected-(J114-Pad5)") (class "Default")
      (node (ref "J114") (pin "5") (pinfunction "5_5") (pintype "passive"))
    )
    (net (code "129") (name "unconnected-(J114-Pad6)") (class "Default")
      (node (ref "J114") (pin "6") (pinfunction "6_6") (pintype "passive"))
    )
  )
)
